# mainboard.net
KiCad netlist of a schematic drawn in EAGLE
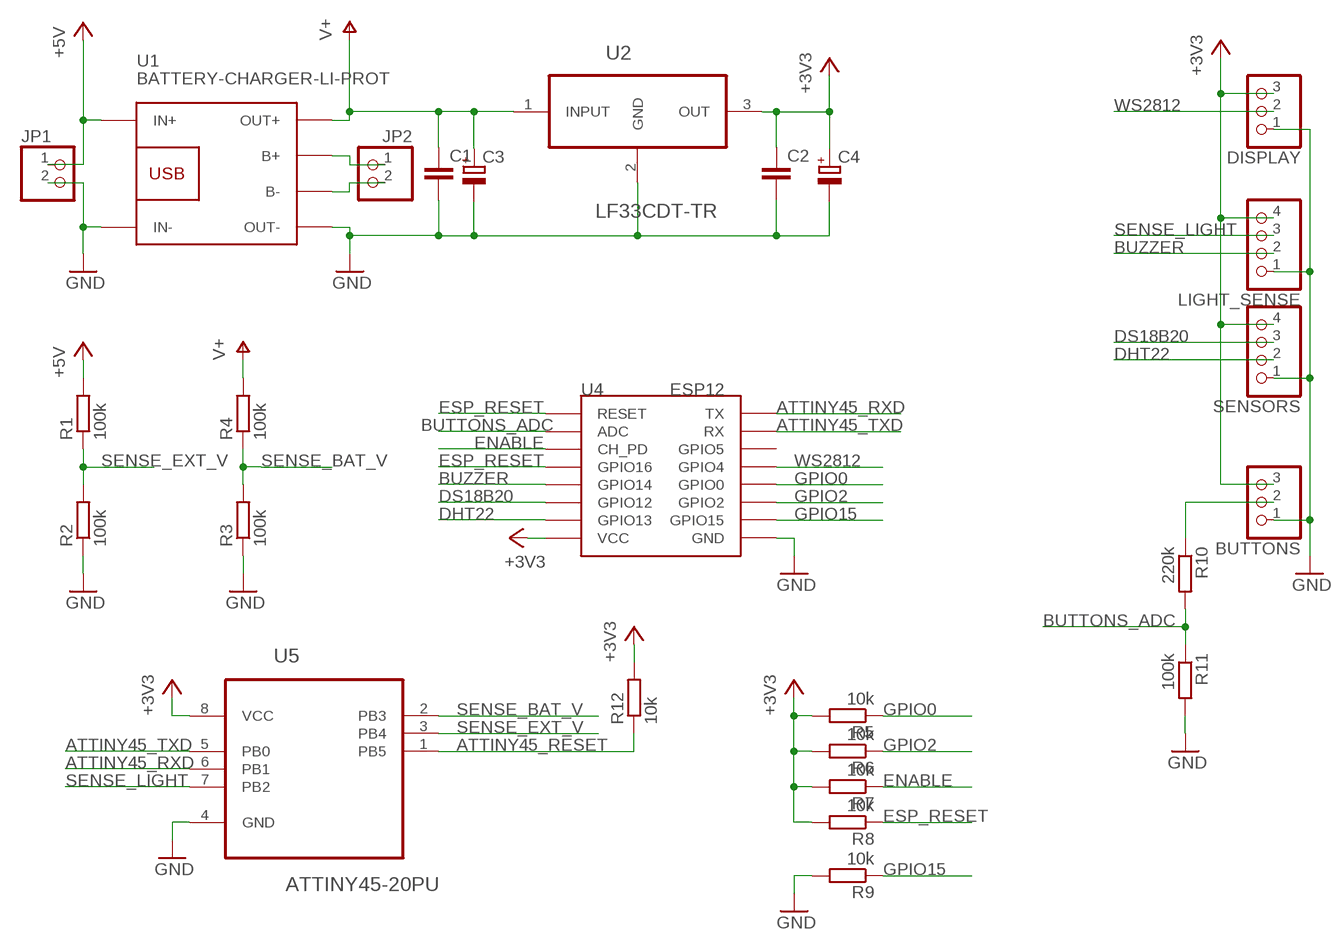
[diagram p0: schematic, sheet 1]

(export (version "E")
  (design (tool "Eeschema 10.0.6"))
  (components
    (comp (ref "BUTTONS")
      (value "PINHD-1X3")
      (footprint "eagle-import:1X03")
      (libsource (lib "eagle-import") (part "PINHD-1X3"))
    )
    (comp (ref "C1")
      (value "C-EUC1206")
      (footprint "eagle-import:C1206")
      (libsource (lib "eagle-import") (part "C-EUC1206"))
    )
    (comp (ref "C2")
      (value "C-EUC1206")
      (footprint "eagle-import:C1206")
      (libsource (lib "eagle-import") (part "C-EUC1206"))
    )
    (comp (ref "C3")
      (value "CPOL-EUE2-5")
      (footprint "eagle-import:E2-5")
      (libsource (lib "eagle-import") (part "CPOL-EUE2-5"))
    )
    (comp (ref "C4")
      (value "CPOL-EUE2-5")
      (footprint "eagle-import:E2-5")
      (libsource (lib "eagle-import") (part "CPOL-EUE2-5"))
    )
    (comp (ref "DISPLAY")
      (value "PINHD-1X3")
      (footprint "eagle-import:1X03")
      (libsource (lib "eagle-import") (part "PINHD-1X3"))
    )
    (comp (ref "JP1")
      (value "PINHD-1X2")
      (footprint "eagle-import:1X02")
      (libsource (lib "eagle-import") (part "PINHD-1X2"))
    )
    (comp (ref "JP2")
      (value "PINHD-1X2")
      (footprint "eagle-import:1X02")
      (libsource (lib "eagle-import") (part "PINHD-1X2"))
    )
    (comp (ref "LIGHT_SENSE")
      (value "PINHD-1X4")
      (footprint "eagle-import:1X04")
      (libsource (lib "eagle-import") (part "PINHD-1X4"))
    )
    (comp (ref "R1")
      (value "100k")
      (footprint "eagle-import:R1206")
      (libsource (lib "eagle-import") (part "R-EU_R1206"))
    )
    (comp (ref "R2")
      (value "100k")
      (footprint "eagle-import:R1206")
      (libsource (lib "eagle-import") (part "R-EU_R1206"))
    )
    (comp (ref "R3")
      (value "100k")
      (footprint "eagle-import:R1206")
      (libsource (lib "eagle-import") (part "R-EU_R1206"))
    )
    (comp (ref "R4")
      (value "100k")
      (footprint "eagle-import:R1206")
      (libsource (lib "eagle-import") (part "R-EU_R1206"))
    )
    (comp (ref "R5")
      (value "10k")
      (footprint "eagle-import:R1206")
      (libsource (lib "eagle-import") (part "R-EU_R1206"))
    )
    (comp (ref "R6")
      (value "10k")
      (footprint "eagle-import:R1206")
      (libsource (lib "eagle-import") (part "R-EU_R1206"))
    )
    (comp (ref "R7")
      (value "10k")
      (footprint "eagle-import:R1206")
      (libsource (lib "eagle-import") (part "R-EU_R1206"))
    )
    (comp (ref "R8")
      (value "10k")
      (footprint "eagle-import:R1206")
      (libsource (lib "eagle-import") (part "R-EU_R1206"))
    )
    (comp (ref "R9")
      (value "10k")
      (footprint "eagle-import:R1206")
      (libsource (lib "eagle-import") (part "R-EU_R1206"))
    )
    (comp (ref "R10")
      (value "220k")
      (footprint "eagle-import:R1206")
      (libsource (lib "eagle-import") (part "R-EU_R1206"))
    )
    (comp (ref "R11")
      (value "100k")
      (footprint "eagle-import:R1206")
      (libsource (lib "eagle-import") (part "R-EU_R1206"))
    )
    (comp (ref "R12")
      (value "10k")
      (footprint "eagle-import:R1206")
      (libsource (lib "eagle-import") (part "R-EU_R1206"))
    )
    (comp (ref "SENSORS")
      (value "PINHD-1X4")
      (footprint "eagle-import:1X04")
      (libsource (lib "eagle-import") (part "PINHD-1X4"))
    )
    (comp (ref "U1")
      (value "BATTERY-CHARGER-LI-PROT")
      (footprint "eagle-import:BATTERY-CHARGER-LI-PROT")
      (libsource (lib "eagle-import") (part "BATTERY-CHARGER-LI-PROT"))
    )
    (comp (ref "U2")
      (value "LF33CDT-TR")
      (footprint "eagle-import:TO228P972X240-3N")
      (fields (field (name "MF") "STMicroelectronics"))
      (libsource (lib "eagle-import") (part "LF33CDT-TR"))
    )
    (comp (ref "U4")
      (value "ESP12")
      (footprint "eagle-import:ESP12")
      (libsource (lib "eagle-import") (part "ESP12"))
    )
    (comp (ref "U5")
      (value "ATTINY45-20PU")
      (footprint "eagle-import:DIP254P762X533-8")
      (fields (field (name "MF") "Microchip"))
      (libsource (lib "eagle-import") (part "ATTINY45-20PU"))
    )
  )
  (nets
    (net (code "1") (name "+3V3") (class "Default")
      (node (ref "BUTTONS") (pin "3") (pinfunction "3_3") (pintype "passive"))
      (node (ref "C2") (pin "1") (pinfunction "1_1") (pintype "passive"))
      (node (ref "C4") (pin "+") (pinfunction "+_+") (pintype "passive"))
      (node (ref "DISPLAY") (pin "3") (pinfunction "3_3") (pintype "passive"))
      (node (ref "LIGHT_SENSE") (pin "4") (pinfunction "4_4") (pintype "passive"))
      (node (ref "R12") (pin "2") (pinfunction "2_2") (pintype "passive"))
      (node (ref "R5") (pin "2") (pinfunction "2_2") (pintype "passive"))
      (node (ref "R6") (pin "2") (pinfunction "2_2") (pintype "passive"))
      (node (ref "R7") (pin "2") (pinfunction "2_2") (pintype "passive"))
      (node (ref "R8") (pin "2") (pinfunction "2_2") (pintype "passive"))
      (node (ref "SENSORS") (pin "4") (pinfunction "4_4") (pintype "passive"))
      (node (ref "U2") (pin "3") (pinfunction "OUT_3") (pintype "output"))
      (node (ref "U4") (pin "VCC") (pinfunction "VCC_VCC") (pintype "bidirectional"))
      (node (ref "U5") (pin "8") (pinfunction "VCC_8") (pintype "power_in"))
    )
    (net (code "2") (name "+5V") (class "Default")
      (node (ref "JP1") (pin "1") (pinfunction "1_1") (pintype "passive"))
      (node (ref "R1") (pin "2") (pinfunction "2_2") (pintype "passive"))
      (node (ref "U1") (pin "IN+") (pinfunction "IN+_IN+") (pintype "bidirectional"))
    )
    (net (code "3") (name "/ATTINY45_RESET") (class "Default")
      (node (ref "R12") (pin "1") (pinfunction "1_1") (pintype "passive"))
      (node (ref "U5") (pin "1") (pinfunction "PB5_1") (pintype "bidirectional"))
    )
    (net (code "4") (name "/ATTINY45_RXD") (class "Default")
      (node (ref "U4") (pin "TX") (pinfunction "TX_TX") (pintype "bidirectional"))
      (node (ref "U5") (pin "6") (pinfunction "PB1_6") (pintype "bidirectional"))
    )
    (net (code "5") (name "/ATTINY45_TXD") (class "Default")
      (node (ref "U4") (pin "RX") (pinfunction "RX_RX") (pintype "bidirectional"))
      (node (ref "U5") (pin "5") (pinfunction "PB0_5") (pintype "bidirectional"))
    )
    (net (code "6") (name "/BUTTONS_ADC") (class "Default")
      (node (ref "R10") (pin "2") (pinfunction "2_2") (pintype "passive"))
      (node (ref "R11") (pin "1") (pinfunction "1_1") (pintype "passive"))
      (node (ref "U4") (pin "ADC") (pinfunction "ADC_ADC") (pintype "bidirectional"))
    )
    (net (code "7") (name "/BUZZER") (class "Default")
      (node (ref "LIGHT_SENSE") (pin "2") (pinfunction "2_2") (pintype "passive"))
      (node (ref "U4") (pin "GPIO14") (pinfunction "GPIO14_GPIO14") (pintype "bidirectional"))
    )
    (net (code "8") (name "/DHT22") (class "Default")
      (node (ref "SENSORS") (pin "2") (pinfunction "2_2") (pintype "passive"))
      (node (ref "U4") (pin "GPIO13") (pinfunction "GPIO13_GPIO13") (pintype "bidirectional"))
    )
    (net (code "9") (name "/DS18B20") (class "Default")
      (node (ref "SENSORS") (pin "3") (pinfunction "3_3") (pintype "passive"))
      (node (ref "U4") (pin "GPIO12") (pinfunction "GPIO12_GPIO12") (pintype "bidirectional"))
    )
    (net (code "10") (name "/ENABLE") (class "Default")
      (node (ref "R7") (pin "1") (pinfunction "1_1") (pintype "passive"))
      (node (ref "U4") (pin "CH_PD") (pinfunction "CH_PD_CH_PD") (pintype "bidirectional"))
    )
    (net (code "11") (name "/ESP_RESET") (class "Default")
      (node (ref "R8") (pin "1") (pinfunction "1_1") (pintype "passive"))
      (node (ref "U4") (pin "GPIO16") (pinfunction "GPIO16_GPIO16") (pintype "bidirectional"))
      (node (ref "U4") (pin "RESET") (pinfunction "RESET_RESET") (pintype "bidirectional"))
    )
    (net (code "12") (name "/GPIO0") (class "Default")
      (node (ref "R5") (pin "1") (pinfunction "1_1") (pintype "passive"))
      (node (ref "U4") (pin "GPIO0") (pinfunction "GPIO0_GPIO0") (pintype "bidirectional"))
    )
    (net (code "13") (name "/GPIO2") (class "Default")
      (node (ref "R6") (pin "1") (pinfunction "1_1") (pintype "passive"))
      (node (ref "U4") (pin "GPIO2") (pinfunction "GPIO2_GPIO2") (pintype "bidirectional"))
    )
    (net (code "14") (name "/GPIO15") (class "Default")
      (node (ref "R9") (pin "1") (pinfunction "1_1") (pintype "passive"))
      (node (ref "U4") (pin "GPIO15") (pinfunction "GPIO15_GPIO15") (pintype "bidirectional"))
    )
    (net (code "15") (name "/SENSE_BAT_V") (class "Default")
      (node (ref "R3") (pin "2") (pinfunction "2_2") (pintype "passive"))
      (node (ref "R4") (pin "1") (pinfunction "1_1") (pintype "passive"))
      (node (ref "U5") (pin "2") (pinfunction "PB3_2") (pintype "bidirectional"))
    )
    (net (code "16") (name "/SENSE_EXT_V") (class "Default")
      (node (ref "R1") (pin "1") (pinfunction "1_1") (pintype "passive"))
      (node (ref "R2") (pin "2") (pinfunction "2_2") (pintype "passive"))
      (node (ref "U5") (pin "3") (pinfunction "PB4_3") (pintype "bidirectional"))
    )
    (net (code "17") (name "/SENSE_LIGHT") (class "Default")
      (node (ref "LIGHT_SENSE") (pin "3") (pinfunction "3_3") (pintype "passive"))
      (node (ref "U5") (pin "7") (pinfunction "PB2_7") (pintype "bidirectional"))
    )
    (net (code "18") (name "/WS2812") (class "Default")
      (node (ref "DISPLAY") (pin "2") (pinfunction "2_2") (pintype "passive"))
      (node (ref "U4") (pin "GPIO5") (pinfunction "GPIO4_GPIO5") (pintype "bidirectional"))
    )
    (net (code "19") (name "GND") (class "Default")
      (node (ref "BUTTONS") (pin "1") (pinfunction "1_1") (pintype "passive"))
      (node (ref "C1") (pin "2") (pinfunction "2_2") (pintype "passive"))
      (node (ref "C2") (pin "2") (pinfunction "2_2") (pintype "passive"))
      (node (ref "C3") (pin "-") (pinfunction "-_-") (pintype "passive"))
      (node (ref "C4") (pin "-") (pinfunction "-_-") (pintype "passive"))
      (node (ref "DISPLAY") (pin "1") (pinfunction "1_1") (pintype "passive"))
      (node (ref "JP1") (pin "2") (pinfunction "2_2") (pintype "passive"))
      (node (ref "LIGHT_SENSE") (pin "1") (pinfunction "1_1") (pintype "passive"))
      (node (ref "R11") (pin "2") (pinfunction "2_2") (pintype "passive"))
      (node (ref "R2") (pin "1") (pinfunction "1_1") (pintype "passive"))
      (node (ref "R3") (pin "1") (pinfunction "1_1") (pintype "passive"))
      (node (ref "R9") (pin "2") (pinfunction "2_2") (pintype "passive"))
      (node (ref "SENSORS") (pin "1") (pinfunction "1_1") (pintype "passive"))
      (node (ref "U1") (pin "IN-") (pinfunction "IN-_IN-") (pintype "bidirectional"))
      (node (ref "U1") (pin "OUT-") (pinfunction "OUT-_OUT-") (pintype "bidirectional"))
      (node (ref "U2") (pin "2") (pinfunction "GND_2") (pintype "passive"))
      (node (ref "U4") (pin "GND") (pinfunction "GND_GND") (pintype "bidirectional"))
      (node (ref "U5") (pin "4") (pinfunction "GND_4") (pintype "passive"))
    )
    (net (code "20") (name "Net-(BUTTONS-Pad2)") (class "Default")
      (node (ref "BUTTONS") (pin "2") (pinfunction "2_2") (pintype "passive"))
      (node (ref "R10") (pin "1") (pinfunction "1_1") (pintype "passive"))
    )
    (net (code "21") (name "Net-(JP2-Pad1)") (class "Default")
      (node (ref "JP2") (pin "1") (pinfunction "1_1") (pintype "passive"))
      (node (ref "U1") (pin "B+") (pinfunction "B+_B+") (pintype "bidirectional"))
    )
    (net (code "22") (name "Net-(JP2-Pad2)") (class "Default")
      (node (ref "JP2") (pin "2") (pinfunction "2_2") (pintype "passive"))
      (node (ref "U1") (pin "B-") (pinfunction "B-_B-") (pintype "bidirectional"))
    )
    (net (code "23") (name "V+") (class "Default")
      (node (ref "C1") (pin "1") (pinfunction "1_1") (pintype "passive"))
      (node (ref "C3") (pin "+") (pinfunction "+_+") (pintype "passive"))
      (node (ref "R4") (pin "2") (pinfunction "2_2") (pintype "passive"))
      (node (ref "U1") (pin "OUT+") (pinfunction "OUT+_OUT+") (pintype "bidirectional"))
      (node (ref "U2") (pin "1") (pinfunction "INPUT_1") (pintype "input"))
    )
    (net (code "24") (name "unconnected-(U4-GPIO5-PadGPIO4)") (class "Default")
      (node (ref "U4") (pin "GPIO4") (pinfunction "GPIO5_GPIO4") (pintype "bidirectional"))
    )
  )
)
